# ESP8266_Xmas_Lights.net
KiCad netlist of a schematic drawn in Altium Designer
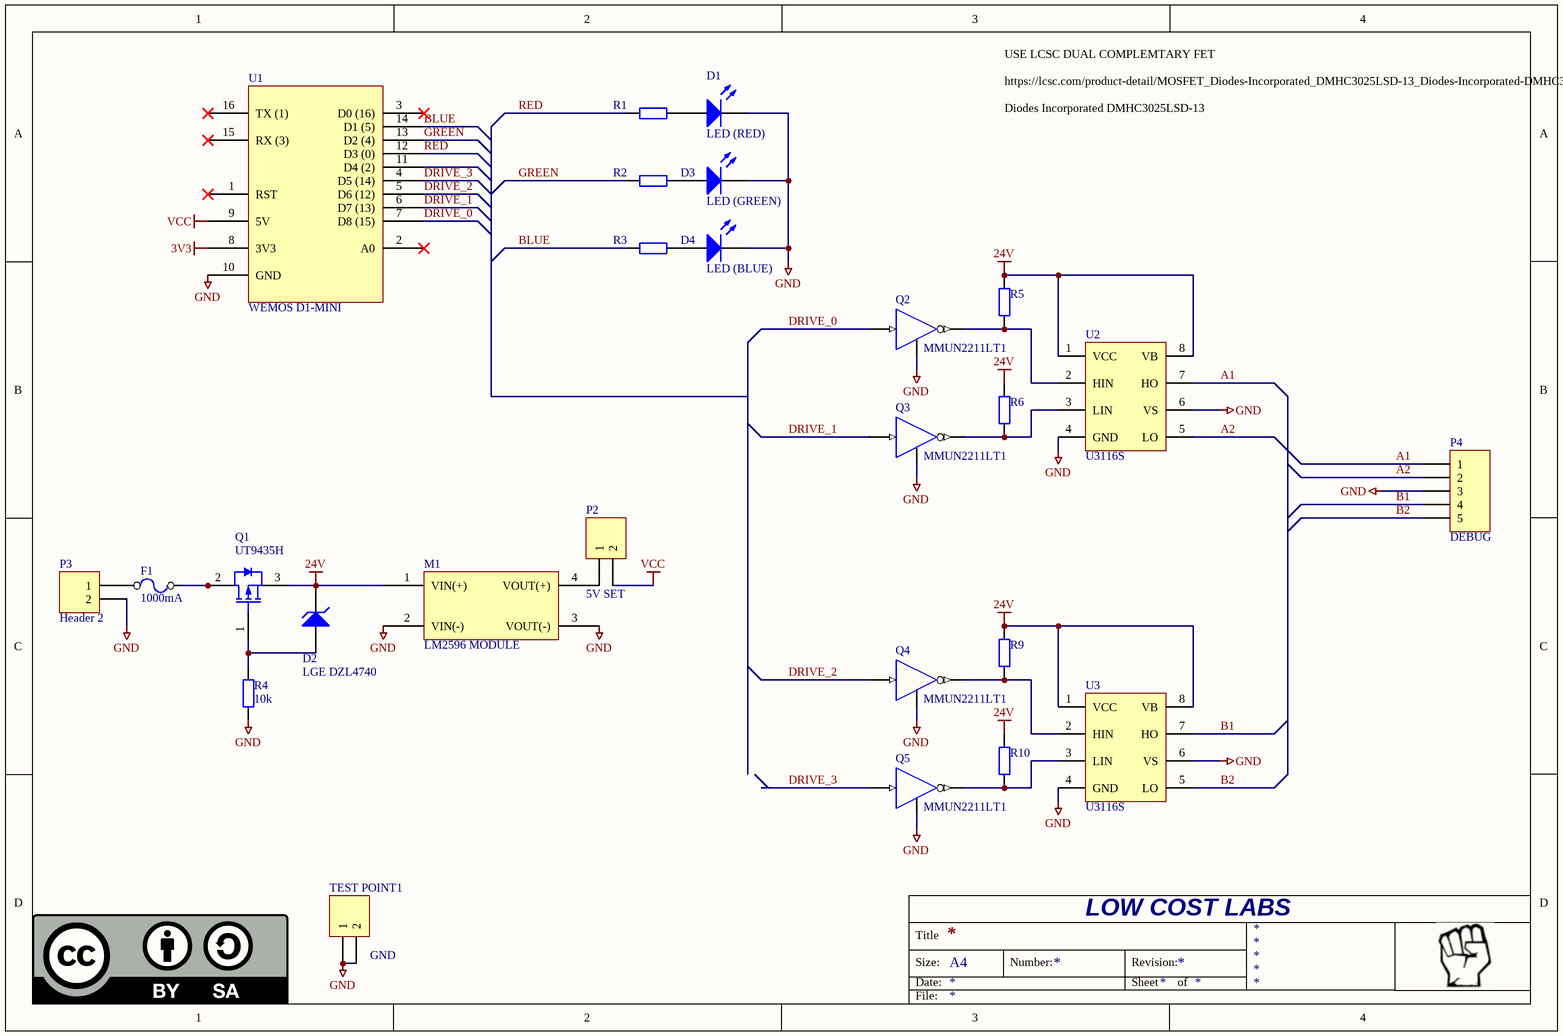
[diagram p0: ESP8266 Xmas Lights.SchDoc]

(export (version "E")
  (design (tool "Eeschema 10.0.6"))
  (components
    (comp (ref "D1")
      (value "LED (RED)")
      (footprint "LED(3D) 3MM VERTICAL (RED)")
      (description "3mm RED LED")
      (fields (field (name "MOUSER PART NO.") "604-WP132XIT") (field (name "FARNELL PART NO.") "1003393"))
      (libsource (lib "NASCO") (part "LED 3mm RED"))
    )
    (comp (ref "D2")
      (value "LGE DZL4740")
      (footprint "SOD-123FL")
      (description "10V 1W 10uA @ 7.6V SOD-123FL Zener Diode")
      (fields (field (name "MANUFACTURER PART NUMBER") "1N4733A"))
      (libsource (lib "WS2812 Xmas Lights") (part "LGE DZL4740"))
    )
    (comp (ref "D3")
      (value "LED (GREEN)")
      (footprint "LED(3D) 3MM VERTICAL (GREEN)")
      (description "3mm RED LED")
      (fields (field (name "MOUSER PART NO.") "604-WP132XIT") (field (name "FARNELL PART NO.") "1003393"))
      (libsource (lib "NASCO") (part "LED 3mm RED"))
    )
    (comp (ref "D4")
      (value "LED (BLUE)")
      (footprint "LED(3D) 3MM VERTICAL (GREEN)")
      (description "3mm RED LED")
      (fields (field (name "MOUSER PART NO.") "604-WP132XIT") (field (name "FARNELL PART NO.") "1003393"))
      (libsource (lib "NASCO") (part "LED 3mm RED"))
    )
    (comp (ref "F1")
      (value "1000mA")
      (footprint "POLYSWITCH 1210")
      (description "PTC 12V POLYFUSE SMT 1210 500mA (1210L110/12WR)")
      (libsource (lib "altium-import") (part "root_0_PTC 12V POLYFUSE SMT 1210 1.10A_"))
    )
    (comp (ref "M1")
      (value "LM2596 MODULE")
      (footprint "LM2596 Module")
      (libsource (lib "Barun Gas Control") (part "LM2596 MODULE"))
    )
    (comp (ref "P2")
      (value "5V SET")
      (footprint "Pin Header 1x2 TH Pitch 2.54mm")
      (description "Header, 2-Pin")
      (fields (field (name "MANUFACTURER") "FCI") (field (name "MANUFACTURER PART NO.") "68020-102"))
      (libsource (lib "") (part "Header 2_1"))
    )
    (comp (ref "P3")
      (value "Header 2")
      (footprint "2 FLYING WIRES")
      (description "Header, 2-Pin")
      (fields (field (name "MANUFACTURER") "FCI") (field (name "MANUFACTURER PART NO.") "68020-102"))
      (libsource (lib "NASCO") (part "Header 2"))
    )
    (comp (ref "P4")
      (value "DEBUG")
      (footprint "5 FLYING WIRES")
      (description "Header, 5 Pin")
      (fields (field (name "MANUFACTURER") "FCI") (field (name "MANUFACTURER PART NO.") "68020-102"))
      (libsource (lib "WS2812 Xmas Lights") (part "Header 5"))
    )
    (comp (ref "Q1")
      (value "UT9435H")
      (footprint "SOT223")
      (description "UT9435H P-CHANNEL ENHANCEMENT MODE")
      (fields (field (name "MANUFACTURER PART NUMBER") "NDP6020P"))
      (libsource (lib "WS2812 Xmas Lights") (part "UT9435H"))
    )
    (comp (ref "Q2")
      (value "MMUN2211LT1")
      (footprint "SOT23-3L")
      (fields
        (field (name "MOUSER PART NO.") "863-MMUN2211LT1G")
        (field (name "FARNELL PART NO.") "9556648RL")
        (field (name "MANUFACTURER") "ON Semiconductor")
      )
      (libsource (lib "NASCO") (part "MMUN221LT1 NPN DIGITAL TRANSISTOR"))
    )
    (comp (ref "Q3")
      (value "MMUN2211LT1")
      (footprint "SOT23-3L")
      (fields
        (field (name "MOUSER PART NO.") "863-MMUN2211LT1G")
        (field (name "FARNELL PART NO.") "9556648RL")
        (field (name "MANUFACTURER") "ON Semiconductor")
      )
      (libsource (lib "NASCO") (part "MMUN221LT1 NPN DIGITAL TRANSISTOR"))
    )
    (comp (ref "Q4")
      (value "MMUN2211LT1")
      (footprint "SOT23-3L")
      (fields
        (field (name "MOUSER PART NO.") "863-MMUN2211LT1G")
        (field (name "FARNELL PART NO.") "9556648RL")
        (field (name "MANUFACTURER") "ON Semiconductor")
      )
      (libsource (lib "NASCO") (part "MMUN221LT1 NPN DIGITAL TRANSISTOR"))
    )
    (comp (ref "Q5")
      (value "MMUN2211LT1")
      (footprint "SOT23-3L")
      (fields
        (field (name "MOUSER PART NO.") "863-MMUN2211LT1G")
        (field (name "FARNELL PART NO.") "9556648RL")
        (field (name "MANUFACTURER") "ON Semiconductor")
      )
      (libsource (lib "NASCO") (part "MMUN221LT1 NPN DIGITAL TRANSISTOR"))
    )
    (comp (ref "R1")
      (value "~")
      (footprint "HAL9100:RESISTOR 0805")
      (description "Resistor")
      (fields (field (name "PUBLISHER") "Altium Limited"))
      (libsource (lib "") (part "Res2_2"))
    )
    (comp (ref "R2")
      (value "~")
      (footprint "HAL9100:RESISTOR 0805")
      (description "Resistor")
      (fields (field (name "PUBLISHER") "Altium Limited"))
      (libsource (lib "") (part "Res2_2"))
    )
    (comp (ref "R3")
      (value "~")
      (footprint "HAL9100:RESISTOR 0805")
      (description "Resistor")
      (fields (field (name "PUBLISHER") "Altium Limited"))
      (libsource (lib "Miscellaneous Devices") (part "Res2"))
    )
    (comp (ref "R4")
      (value "10k")
      (footprint "HAL9100:RESISTOR 0805")
      (description "Resistor")
      (fields (field (name "PUBLISHER") "Altium Limited"))
      (libsource (lib "") (part "Res2_1"))
    )
    (comp (ref "R5")
      (value "~")
      (footprint "HAL9100:RESISTOR 0805")
      (description "Resistor")
      (fields (field (name "PUBLISHER") "Altium Limited"))
      (libsource (lib "") (part "Res2_1"))
    )
    (comp (ref "R6")
      (value "~")
      (footprint "HAL9100:RESISTOR 0805")
      (description "Resistor")
      (fields (field (name "PUBLISHER") "Altium Limited"))
      (libsource (lib "") (part "Res2_1"))
    )
    (comp (ref "R9")
      (value "~")
      (footprint "HAL9100:RESISTOR 0805")
      (description "Resistor")
      (fields (field (name "PUBLISHER") "Altium Limited"))
      (libsource (lib "") (part "Res2_1"))
    )
    (comp (ref "R10")
      (value "~")
      (footprint "HAL9100:RESISTOR 0805")
      (description "Resistor")
      (fields (field (name "PUBLISHER") "Altium Limited"))
      (libsource (lib "") (part "Res2_1"))
    )
    (comp (ref "TEST POINT1")
      (value "GND")
      (footprint "Pin Header 1x2 TH Pitch 2.54mm")
      (description "Header, 2-Pin")
      (fields (field (name "MANUFACTURER") "FCI") (field (name "MANUFACTURER PART NO.") "68020-102"))
      (libsource (lib "") (part "Header 2_1"))
    )
    (comp (ref "U1")
      (value "WEMOS D1-MINI")
      (footprint "WEMOS PRO MINI")
      (libsource (lib "EnvNode") (part "WEMOS"))
    )
    (comp (ref "U2")
      (value "U3116S")
      (footprint "SO-8")
      (description "U3116S High Current IO+/- 1.2/1.5A HALF-BRIDGE DRIVER")
      (libsource (lib "WS2812 Xmas Lights") (part "U3116S"))
    )
    (comp (ref "U3")
      (value "U3116S")
      (footprint "SO-8")
      (description "U3116S High Current IO+/- 1.2/1.5A HALF-BRIDGE DRIVER")
      (libsource (lib "WS2812 Xmas Lights") (part "U3116S"))
    )
  )
  (nets
    (net (code "1") (name "/A1") (class "Default")
      (node (ref "P4") (pin "1") (pinfunction "1_1") (pintype "passive"))
      (node (ref "U2") (pin "7") (pinfunction "HO_7") (pintype "passive"))
    )
    (net (code "2") (name "/A2") (class "Default")
      (node (ref "P4") (pin "2") (pinfunction "2_2") (pintype "passive"))
      (node (ref "U2") (pin "5") (pinfunction "LO_5") (pintype "passive"))
    )
    (net (code "3") (name "/B1") (class "Default")
      (node (ref "P4") (pin "4") (pinfunction "4_4") (pintype "passive"))
      (node (ref "U3") (pin "7") (pinfunction "HO_7") (pintype "passive"))
    )
    (net (code "4") (name "/B2") (class "Default")
      (node (ref "P4") (pin "5") (pinfunction "5_5") (pintype "passive"))
      (node (ref "U3") (pin "5") (pinfunction "LO_5") (pintype "passive"))
    )
    (net (code "5") (name "/BLUE") (class "Default")
      (node (ref "R3") (pin "2") (pinfunction "2_2") (pintype "passive"))
      (node (ref "U1") (pin "14") (pinfunction "D1_(5)_14") (pintype "passive"))
    )
    (net (code "6") (name "/DRIVE_0") (class "Default")
      (node (ref "Q2") (pin "1") (pinfunction "B_1") (pintype "input"))
      (node (ref "U1") (pin "7") (pinfunction "D8_(15)_7") (pintype "passive"))
    )
    (net (code "7") (name "/DRIVE_1") (class "Default")
      (node (ref "Q3") (pin "1") (pinfunction "B_1") (pintype "input"))
      (node (ref "U1") (pin "6") (pinfunction "D7_(13)_6") (pintype "passive"))
    )
    (net (code "8") (name "/DRIVE_2") (class "Default")
      (node (ref "Q4") (pin "1") (pinfunction "B_1") (pintype "input"))
      (node (ref "U1") (pin "5") (pinfunction "D6_(12)_5") (pintype "passive"))
    )
    (net (code "9") (name "/DRIVE_3") (class "Default")
      (node (ref "Q5") (pin "1") (pinfunction "B_1") (pintype "input"))
      (node (ref "U1") (pin "4") (pinfunction "D5_(14)_4") (pintype "passive"))
    )
    (net (code "10") (name "/GREEN") (class "Default")
      (node (ref "R2") (pin "1") (pinfunction "1_1") (pintype "passive"))
      (node (ref "U1") (pin "13") (pinfunction "D2_(4)_13") (pintype "passive"))
    )
    (net (code "11") (name "/RED") (class "Default")
      (node (ref "R1") (pin "1") (pinfunction "1_1") (pintype "passive"))
      (node (ref "U1") (pin "12") (pinfunction "D3_(0)_12") (pintype "passive"))
    )
    (net (code "12") (name "3V3") (class "Default")
      (node (ref "U1") (pin "8") (pinfunction "3V3_8") (pintype "passive"))
    )
    (net (code "13") (name "24V") (class "Default")
      (node (ref "D2") (pin "1") (pinfunction "K_1") (pintype "passive"))
      (node (ref "M1") (pin "1") (pinfunction "VIN(+)_1") (pintype "passive"))
      (node (ref "Q1") (pin "3") (pinfunction "S_3") (pintype "passive"))
      (node (ref "R10") (pin "2") (pinfunction "2_2") (pintype "passive"))
      (node (ref "R5") (pin "2") (pinfunction "2_2") (pintype "passive"))
      (node (ref "R6") (pin "2") (pinfunction "2_2") (pintype "passive"))
      (node (ref "R9") (pin "2") (pinfunction "2_2") (pintype "passive"))
      (node (ref "U2") (pin "1") (pinfunction "VCC_1") (pintype "passive"))
      (node (ref "U2") (pin "8") (pinfunction "VB_8") (pintype "passive"))
      (node (ref "U3") (pin "1") (pinfunction "VCC_1") (pintype "passive"))
      (node (ref "U3") (pin "8") (pinfunction "VB_8") (pintype "passive"))
    )
    (net (code "14") (name "GND") (class "Default")
      (node (ref "D1") (pin "2") (pinfunction "K_2") (pintype "passive"))
      (node (ref "D3") (pin "2") (pinfunction "K_2") (pintype "passive"))
      (node (ref "D4") (pin "2") (pinfunction "K_2") (pintype "passive"))
      (node (ref "M1") (pin "2") (pinfunction "VIN(-)_2") (pintype "passive"))
      (node (ref "M1") (pin "3") (pinfunction "VOUT(-)_3") (pintype "passive"))
      (node (ref "P3") (pin "2") (pinfunction "2_2") (pintype "passive"))
      (node (ref "P4") (pin "3") (pinfunction "3_3") (pintype "passive"))
      (node (ref "Q2") (pin "2") (pinfunction "E_2") (pintype "passive"))
      (node (ref "Q3") (pin "2") (pinfunction "E_2") (pintype "passive"))
      (node (ref "Q4") (pin "2") (pinfunction "E_2") (pintype "passive"))
      (node (ref "Q5") (pin "2") (pinfunction "E_2") (pintype "passive"))
      (node (ref "R4") (pin "1") (pinfunction "1_1") (pintype "passive"))
      (node (ref "TEST POINT1") (pin "1") (pinfunction "1_1") (pintype "passive"))
      (node (ref "TEST POINT1") (pin "2") (pinfunction "2_2") (pintype "passive"))
      (node (ref "U1") (pin "10") (pinfunction "GND_10") (pintype "passive"))
      (node (ref "U2") (pin "4") (pinfunction "GND_4") (pintype "passive"))
      (node (ref "U2") (pin "6") (pinfunction "VS_6") (pintype "passive"))
      (node (ref "U3") (pin "4") (pinfunction "GND_4") (pintype "passive"))
      (node (ref "U3") (pin "6") (pinfunction "VS_6") (pintype "passive"))
    )
    (net (code "15") (name "Net-(D1-A)") (class "Default")
      (node (ref "D1") (pin "1") (pinfunction "A_1") (pintype "passive"))
      (node (ref "R1") (pin "2") (pinfunction "2_2") (pintype "passive"))
    )
    (net (code "16") (name "Net-(D2-A)") (class "Default")
      (node (ref "D2") (pin "2") (pinfunction "A_2") (pintype "passive"))
      (node (ref "Q1") (pin "1") (pinfunction "G_1") (pintype "passive"))
      (node (ref "R4") (pin "2") (pinfunction "2_2") (pintype "passive"))
    )
    (net (code "17") (name "Net-(D3-A)") (class "Default")
      (node (ref "D3") (pin "1") (pinfunction "A_1") (pintype "passive"))
      (node (ref "R2") (pin "2") (pinfunction "2_2") (pintype "passive"))
    )
    (net (code "18") (name "Net-(D4-A)") (class "Default")
      (node (ref "D4") (pin "1") (pinfunction "A_1") (pintype "passive"))
      (node (ref "R3") (pin "1") (pinfunction "1_1") (pintype "passive"))
    )
    (net (code "19") (name "Net-(F1-Pad1)") (class "Default")
      (node (ref "F1") (pin "1") (pinfunction "1_1") (pintype "passive"))
      (node (ref "P3") (pin "1") (pinfunction "1_1") (pintype "passive"))
    )
    (net (code "20") (name "Net-(F1-Pad2)") (class "Default")
      (node (ref "F1") (pin "2") (pinfunction "2_2") (pintype "passive"))
      (node (ref "Q1") (pin "2") (pinfunction "D_2") (pintype "passive"))
      (node (ref "Q1") (pin "4") (pinfunction "D_4") (pintype "passive"))
    )
    (net (code "21") (name "Net-(M1-VOUT(+))") (class "Default")
      (node (ref "M1") (pin "4") (pinfunction "VOUT(+)_4") (pintype "passive"))
      (node (ref "P2") (pin "1") (pinfunction "1_1") (pintype "passive"))
    )
    (net (code "22") (name "Net-(Q2-C)") (class "Default")
      (node (ref "Q2") (pin "3") (pinfunction "C_3") (pintype "output"))
      (node (ref "R5") (pin "1") (pinfunction "1_1") (pintype "passive"))
      (node (ref "U2") (pin "2") (pinfunction "HIN_2") (pintype "passive"))
    )
    (net (code "23") (name "Net-(Q3-C)") (class "Default")
      (node (ref "Q3") (pin "3") (pinfunction "C_3") (pintype "output"))
      (node (ref "R6") (pin "1") (pinfunction "1_1") (pintype "passive"))
      (node (ref "U2") (pin "3") (pinfunction "LIN_3") (pintype "passive"))
    )
    (net (code "24") (name "Net-(Q4-C)") (class "Default")
      (node (ref "Q4") (pin "3") (pinfunction "C_3") (pintype "output"))
      (node (ref "R9") (pin "1") (pinfunction "1_1") (pintype "passive"))
      (node (ref "U3") (pin "2") (pinfunction "HIN_2") (pintype "passive"))
    )
    (net (code "25") (name "Net-(Q5-C)") (class "Default")
      (node (ref "Q5") (pin "3") (pinfunction "C_3") (pintype "output"))
      (node (ref "R10") (pin "1") (pinfunction "1_1") (pintype "passive"))
      (node (ref "U3") (pin "3") (pinfunction "LIN_3") (pintype "passive"))
    )
    (net (code "26") (name "VCC") (class "Default")
      (node (ref "P2") (pin "2") (pinfunction "2_2") (pintype "passive"))
      (node (ref "U1") (pin "9") (pinfunction "5V_9") (pintype "passive"))
    )
    (net (code "27") (name "unconnected-(U1-A0-Pad2)") (class "Default")
      (node (ref "U1") (pin "2") (pinfunction "A0_2") (pintype "passive+no_connect"))
    )
    (net (code "28") (name "unconnected-(U1-D0_(16)-Pad3)") (class "Default")
      (node (ref "U1") (pin "3") (pinfunction "D0_(16)_3") (pintype "passive+no_connect"))
    )
    (net (code "29") (name "unconnected-(U1-D4_(2)-Pad11)") (class "Default")
      (node (ref "U1") (pin "11") (pinfunction "D4_(2)_11") (pintype "passive"))
    )
    (net (code "30") (name "unconnected-(U1-RST-Pad1)") (class "Default")
      (node (ref "U1") (pin "1") (pinfunction "RST_1") (pintype "passive+no_connect"))
    )
    (net (code "31") (name "unconnected-(U1-RX_(3)-Pad15)") (class "Default")
      (node (ref "U1") (pin "15") (pinfunction "RX_(3)_15") (pintype "passive+no_connect"))
    )
    (net (code "32") (name "unconnected-(U1-TX_(1)-Pad16)") (class "Default")
      (node (ref "U1") (pin "16") (pinfunction "TX_(1)_16") (pintype "passive+no_connect"))
    )
  )
)
